# GPS_Board_Rev_C.net
KiCad netlist of a schematic drawn in EAGLE
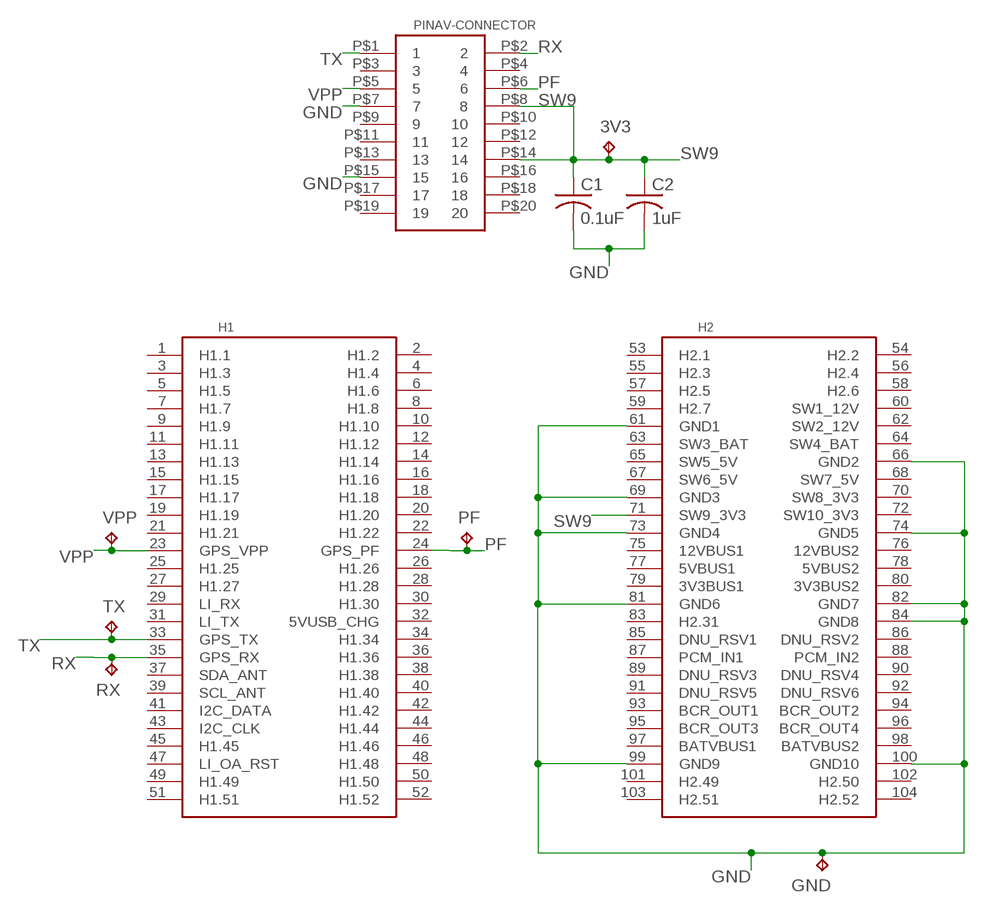
[diagram p0: schematic, sheet 1]

(export (version "E")
  (design (tool "Eeschema 10.0.6"))
  (components
    (comp (ref "3V3")
      (value "TPTP10SQ")
      (footprint "eagle-import:TP10SQ")
      (libsource (lib "eagle-import") (part "TPTP10SQ"))
    )
    (comp (ref "C1")
      (value "0.1uF")
      (footprint "eagle-import:C0805")
      (libsource (lib "eagle-import") (part "C-USC0805"))
    )
    (comp (ref "C2")
      (value "1uF")
      (footprint "eagle-import:C0805")
      (libsource (lib "eagle-import") (part "C-USC0805"))
    )
    (comp (ref "GND")
      (value "TPTP10SQ")
      (footprint "eagle-import:TP10SQ")
      (libsource (lib "eagle-import") (part "TPTP10SQ"))
    )
    (comp (ref "PF")
      (value "TPTP10SQ")
      (footprint "eagle-import:TP10SQ")
      (libsource (lib "eagle-import") (part "TPTP10SQ"))
    )
    (comp (ref "PINAV-CONNECTOR")
      (value "HLE-110-02-X-DVHLE-110-X-DV-PE-BA")
      (footprint "eagle-import:HLE-110-02-X-DV-PE-BE")
      (libsource (lib "eagle-import") (part "HLE-110-02-X-DVHLE-110-X-DV-PE-BA"))
    )
    (comp (ref "RX")
      (value "TPTP10SQ")
      (footprint "eagle-import:TP10SQ")
      (libsource (lib "eagle-import") (part "TPTP10SQ"))
    )
    (comp (ref "TX")
      (value "TPTP10SQ")
      (footprint "eagle-import:TP10SQ")
      (libsource (lib "eagle-import") (part "TPTP10SQ"))
    )
    (comp (ref "U$2")
      (value "PC104_NO_DIMENSION")
      (footprint "eagle-import:PC104_NO_DIMENSION")
      (libsource (lib "eagle-import") (part "PC104_NO_DIMENSION"))
    )
    (comp (ref "VPP")
      (value "TPTP10SQ")
      (footprint "eagle-import:TP10SQ")
      (libsource (lib "eagle-import") (part "TPTP10SQ"))
    )
  )
  (nets
    (net (code "1") (name "/GND") (class "Default")
      (node (ref "C1") (pin "2") (pinfunction "2_2") (pintype "passive"))
      (node (ref "C2") (pin "2") (pinfunction "2_2") (pintype "passive"))
      (node (ref "GND") (pin "TP") (pinfunction "TP_TP") (pintype "input"))
      (node (ref "PINAV-CONNECTOR") (pin "P$15") (pinfunction "15_P$15") (pintype "bidirectional"))
      (node (ref "PINAV-CONNECTOR") (pin "P$7") (pinfunction "7_P$7") (pintype "bidirectional"))
      (node (ref "U$2") (pin "100") (pinfunction "GND10_100") (pintype "bidirectional"))
      (node (ref "U$2") (pin "61") (pinfunction "GND1_61") (pintype "bidirectional"))
      (node (ref "U$2") (pin "66") (pinfunction "GND2_66") (pintype "bidirectional"))
      (node (ref "U$2") (pin "69") (pinfunction "GND3_69") (pintype "bidirectional"))
      (node (ref "U$2") (pin "73") (pinfunction "GND4_73") (pintype "bidirectional"))
      (node (ref "U$2") (pin "74") (pinfunction "GND5_74") (pintype "bidirectional"))
      (node (ref "U$2") (pin "81") (pinfunction "GND6_81") (pintype "bidirectional"))
      (node (ref "U$2") (pin "82") (pinfunction "GND7_82") (pintype "bidirectional"))
      (node (ref "U$2") (pin "84") (pinfunction "GND8_84") (pintype "bidirectional"))
      (node (ref "U$2") (pin "99") (pinfunction "GND9_99") (pintype "bidirectional"))
    )
    (net (code "2") (name "/PF") (class "Default")
      (node (ref "PF") (pin "TP") (pinfunction "TP_TP") (pintype "input"))
      (node (ref "PINAV-CONNECTOR") (pin "P$6") (pinfunction "6_P$6") (pintype "bidirectional"))
      (node (ref "U$2") (pin "24") (pinfunction "GPS_PF_24") (pintype "bidirectional"))
    )
    (net (code "3") (name "/RX") (class "Default")
      (node (ref "PINAV-CONNECTOR") (pin "P$2") (pinfunction "2_P$2") (pintype "bidirectional"))
      (node (ref "RX") (pin "TP") (pinfunction "TP_TP") (pintype "input"))
      (node (ref "U$2") (pin "35") (pinfunction "GPS_RX_35") (pintype "bidirectional"))
    )
    (net (code "4") (name "/SW9") (class "Default")
      (node (ref "3V3") (pin "TP") (pinfunction "TP_TP") (pintype "input"))
      (node (ref "C1") (pin "1") (pinfunction "1_1") (pintype "passive"))
      (node (ref "C2") (pin "1") (pinfunction "1_1") (pintype "passive"))
      (node (ref "PINAV-CONNECTOR") (pin "P$14") (pinfunction "14_P$14") (pintype "bidirectional"))
      (node (ref "PINAV-CONNECTOR") (pin "P$8") (pinfunction "8_P$8") (pintype "bidirectional"))
      (node (ref "U$2") (pin "71") (pinfunction "SW9_3V3_71") (pintype "bidirectional"))
    )
    (net (code "5") (name "/TX") (class "Default")
      (node (ref "PINAV-CONNECTOR") (pin "P$1") (pinfunction "1_P$1") (pintype "bidirectional"))
      (node (ref "TX") (pin "TP") (pinfunction "TP_TP") (pintype "input"))
      (node (ref "U$2") (pin "33") (pinfunction "GPS_TX_33") (pintype "bidirectional"))
    )
    (net (code "6") (name "/VPP") (class "Default")
      (node (ref "PINAV-CONNECTOR") (pin "P$5") (pinfunction "5_P$5") (pintype "bidirectional"))
      (node (ref "U$2") (pin "23") (pinfunction "GPS_VPP_23") (pintype "bidirectional"))
      (node (ref "VPP") (pin "TP") (pinfunction "TP_TP") (pintype "input"))
    )
    (net (code "7") (name "unconnected-(PINAV-CONNECTOR-3-PadP$3)") (class "Default")
      (node (ref "PINAV-CONNECTOR") (pin "P$3") (pinfunction "3_P$3") (pintype "bidirectional"))
    )
    (net (code "8") (name "unconnected-(PINAV-CONNECTOR-4-PadP$4)") (class "Default")
      (node (ref "PINAV-CONNECTOR") (pin "P$4") (pinfunction "4_P$4") (pintype "bidirectional"))
    )
    (net (code "9") (name "unconnected-(PINAV-CONNECTOR-9-PadP$9)") (class "Default")
      (node (ref "PINAV-CONNECTOR") (pin "P$9") (pinfunction "9_P$9") (pintype "bidirectional"))
    )
    (net (code "10") (name "unconnected-(PINAV-CONNECTOR-10-PadP$10)") (class "Default")
      (node (ref "PINAV-CONNECTOR") (pin "P$10") (pinfunction "10_P$10") (pintype "bidirectional"))
    )
    (net (code "11") (name "unconnected-(PINAV-CONNECTOR-11-PadP$11)") (class "Default")
      (node (ref "PINAV-CONNECTOR") (pin "P$11") (pinfunction "11_P$11") (pintype "bidirectional"))
    )
    (net (code "12") (name "unconnected-(PINAV-CONNECTOR-12-PadP$12)") (class "Default")
      (node (ref "PINAV-CONNECTOR") (pin "P$12") (pinfunction "12_P$12") (pintype "bidirectional"))
    )
    (net (code "13") (name "unconnected-(PINAV-CONNECTOR-13-PadP$13)") (class "Default")
      (node (ref "PINAV-CONNECTOR") (pin "P$13") (pinfunction "13_P$13") (pintype "bidirectional"))
    )
    (net (code "14") (name "unconnected-(PINAV-CONNECTOR-16-PadP$16)") (class "Default")
      (node (ref "PINAV-CONNECTOR") (pin "P$16") (pinfunction "16_P$16") (pintype "bidirectional"))
    )
    (net (code "15") (name "unconnected-(PINAV-CONNECTOR-17-PadP$17)") (class "Default")
      (node (ref "PINAV-CONNECTOR") (pin "P$17") (pinfunction "17_P$17") (pintype "bidirectional"))
    )
    (net (code "16") (name "unconnected-(PINAV-CONNECTOR-18-PadP$18)") (class "Default")
      (node (ref "PINAV-CONNECTOR") (pin "P$18") (pinfunction "18_P$18") (pintype "bidirectional"))
    )
    (net (code "17") (name "unconnected-(PINAV-CONNECTOR-19-PadP$19)") (class "Default")
      (node (ref "PINAV-CONNECTOR") (pin "P$19") (pinfunction "19_P$19") (pintype "bidirectional"))
    )
    (net (code "18") (name "unconnected-(PINAV-CONNECTOR-20-PadP$20)") (class "Default")
      (node (ref "PINAV-CONNECTOR") (pin "P$20") (pinfunction "20_P$20") (pintype "bidirectional"))
    )
    (net (code "19") (name "unconnected-(U$2-3V3BUS1-Pad79)") (class "Default")
      (node (ref "U$2") (pin "79") (pinfunction "3V3BUS1_79") (pintype "bidirectional"))
    )
    (net (code "20") (name "unconnected-(U$2-3V3BUS2-Pad80)") (class "Default")
      (node (ref "U$2") (pin "80") (pinfunction "3V3BUS2_80") (pintype "bidirectional"))
    )
    (net (code "21") (name "unconnected-(U$2-5VBUS1-Pad77)") (class "Default")
      (node (ref "U$2") (pin "77") (pinfunction "5VBUS1_77") (pintype "bidirectional"))
    )
    (net (code "22") (name "unconnected-(U$2-5VBUS2-Pad78)") (class "Default")
      (node (ref "U$2") (pin "78") (pinfunction "5VBUS2_78") (pintype "bidirectional"))
    )
    (net (code "23") (name "unconnected-(U$2-5VUSB_CHG-Pad32)") (class "Default")
      (node (ref "U$2") (pin "32") (pinfunction "5VUSB_CHG_32") (pintype "bidirectional"))
    )
    (net (code "24") (name "unconnected-(U$2-12VBUS1-Pad75)") (class "Default")
      (node (ref "U$2") (pin "75") (pinfunction "12VBUS1_75") (pintype "bidirectional"))
    )
    (net (code "25") (name "unconnected-(U$2-12VBUS2-Pad76)") (class "Default")
      (node (ref "U$2") (pin "76") (pinfunction "12VBUS2_76") (pintype "bidirectional"))
    )
    (net (code "26") (name "unconnected-(U$2-BATVBUS1-Pad97)") (class "Default")
      (node (ref "U$2") (pin "97") (pinfunction "BATVBUS1_97") (pintype "bidirectional"))
    )
    (net (code "27") (name "unconnected-(U$2-BATVBUS2-Pad98)") (class "Default")
      (node (ref "U$2") (pin "98") (pinfunction "BATVBUS2_98") (pintype "bidirectional"))
    )
    (net (code "28") (name "unconnected-(U$2-BCR_OUT1-Pad93)") (class "Default")
      (node (ref "U$2") (pin "93") (pinfunction "BCR_OUT1_93") (pintype "bidirectional"))
    )
    (net (code "29") (name "unconnected-(U$2-BCR_OUT2-Pad94)") (class "Default")
      (node (ref "U$2") (pin "94") (pinfunction "BCR_OUT2_94") (pintype "bidirectional"))
    )
    (net (code "30") (name "unconnected-(U$2-BCR_OUT3-Pad95)") (class "Default")
      (node (ref "U$2") (pin "95") (pinfunction "BCR_OUT3_95") (pintype "bidirectional"))
    )
    (net (code "31") (name "unconnected-(U$2-BCR_OUT4-Pad96)") (class "Default")
      (node (ref "U$2") (pin "96") (pinfunction "BCR_OUT4_96") (pintype "bidirectional"))
    )
    (net (code "32") (name "unconnected-(U$2-DNU_RSV1-Pad85)") (class "Default")
      (node (ref "U$2") (pin "85") (pinfunction "DNU_RSV1_85") (pintype "bidirectional"))
    )
    (net (code "33") (name "unconnected-(U$2-DNU_RSV2-Pad86)") (class "Default")
      (node (ref "U$2") (pin "86") (pinfunction "DNU_RSV2_86") (pintype "bidirectional"))
    )
    (net (code "34") (name "unconnected-(U$2-DNU_RSV3-Pad89)") (class "Default")
      (node (ref "U$2") (pin "89") (pinfunction "DNU_RSV3_89") (pintype "bidirectional"))
    )
    (net (code "35") (name "unconnected-(U$2-DNU_RSV4-Pad90)") (class "Default")
      (node (ref "U$2") (pin "90") (pinfunction "DNU_RSV4_90") (pintype "bidirectional"))
    )
    (net (code "36") (name "unconnected-(U$2-DNU_RSV5-Pad91)") (class "Default")
      (node (ref "U$2") (pin "91") (pinfunction "DNU_RSV5_91") (pintype "bidirectional"))
    )
    (net (code "37") (name "unconnected-(U$2-DNU_RSV6-Pad92)") (class "Default")
      (node (ref "U$2") (pin "92") (pinfunction "DNU_RSV6_92") (pintype "bidirectional"))
    )
    (net (code "38") (name "unconnected-(U$2-H1.1-Pad1)") (class "Default")
      (node (ref "U$2") (pin "1") (pinfunction "H1.1_1") (pintype "bidirectional"))
    )
    (net (code "39") (name "unconnected-(U$2-H1.2-Pad2)") (class "Default")
      (node (ref "U$2") (pin "2") (pinfunction "H1.2_2") (pintype "bidirectional"))
    )
    (net (code "40") (name "unconnected-(U$2-H1.3-Pad3)") (class "Default")
      (node (ref "U$2") (pin "3") (pinfunction "H1.3_3") (pintype "bidirectional"))
    )
    (net (code "41") (name "unconnected-(U$2-H1.4-Pad4)") (class "Default")
      (node (ref "U$2") (pin "4") (pinfunction "H1.4_4") (pintype "bidirectional"))
    )
    (net (code "42") (name "unconnected-(U$2-H1.5-Pad5)") (class "Default")
      (node (ref "U$2") (pin "5") (pinfunction "H1.5_5") (pintype "bidirectional"))
    )
    (net (code "43") (name "unconnected-(U$2-H1.6-Pad6)") (class "Default")
      (node (ref "U$2") (pin "6") (pinfunction "H1.6_6") (pintype "bidirectional"))
    )
    (net (code "44") (name "unconnected-(U$2-H1.7-Pad7)") (class "Default")
      (node (ref "U$2") (pin "7") (pinfunction "H1.7_7") (pintype "bidirectional"))
    )
    (net (code "45") (name "unconnected-(U$2-H1.8-Pad8)") (class "Default")
      (node (ref "U$2") (pin "8") (pinfunction "H1.8_8") (pintype "bidirectional"))
    )
    (net (code "46") (name "unconnected-(U$2-H1.9-Pad9)") (class "Default")
      (node (ref "U$2") (pin "9") (pinfunction "H1.9_9") (pintype "bidirectional"))
    )
    (net (code "47") (name "unconnected-(U$2-H1.10-Pad10)") (class "Default")
      (node (ref "U$2") (pin "10") (pinfunction "H1.10_10") (pintype "bidirectional"))
    )
    (net (code "48") (name "unconnected-(U$2-H1.11-Pad11)") (class "Default")
      (node (ref "U$2") (pin "11") (pinfunction "H1.11_11") (pintype "bidirectional"))
    )
    (net (code "49") (name "unconnected-(U$2-H1.12-Pad12)") (class "Default")
      (node (ref "U$2") (pin "12") (pinfunction "H1.12_12") (pintype "bidirectional"))
    )
    (net (code "50") (name "unconnected-(U$2-H1.13-Pad13)") (class "Default")
      (node (ref "U$2") (pin "13") (pinfunction "H1.13_13") (pintype "bidirectional"))
    )
    (net (code "51") (name "unconnected-(U$2-H1.14-Pad14)") (class "Default")
      (node (ref "U$2") (pin "14") (pinfunction "H1.14_14") (pintype "bidirectional"))
    )
    (net (code "52") (name "unconnected-(U$2-H1.15-Pad15)") (class "Default")
      (node (ref "U$2") (pin "15") (pinfunction "H1.15_15") (pintype "bidirectional"))
    )
    (net (code "53") (name "unconnected-(U$2-H1.16-Pad16)") (class "Default")
      (node (ref "U$2") (pin "16") (pinfunction "H1.16_16") (pintype "bidirectional"))
    )
    (net (code "54") (name "unconnected-(U$2-H1.17-Pad17)") (class "Default")
      (node (ref "U$2") (pin "17") (pinfunction "H1.17_17") (pintype "bidirectional"))
    )
    (net (code "55") (name "unconnected-(U$2-H1.18-Pad18)") (class "Default")
      (node (ref "U$2") (pin "18") (pinfunction "H1.18_18") (pintype "bidirectional"))
    )
    (net (code "56") (name "unconnected-(U$2-H1.19-Pad19)") (class "Default")
      (node (ref "U$2") (pin "19") (pinfunction "H1.19_19") (pintype "bidirectional"))
    )
    (net (code "57") (name "unconnected-(U$2-H1.20-Pad20)") (class "Default")
      (node (ref "U$2") (pin "20") (pinfunction "H1.20_20") (pintype "bidirectional"))
    )
    (net (code "58") (name "unconnected-(U$2-H1.21-Pad21)") (class "Default")
      (node (ref "U$2") (pin "21") (pinfunction "H1.21_21") (pintype "bidirectional"))
    )
    (net (code "59") (name "unconnected-(U$2-H1.22-Pad22)") (class "Default")
      (node (ref "U$2") (pin "22") (pinfunction "H1.22_22") (pintype "bidirectional"))
    )
    (net (code "60") (name "unconnected-(U$2-H1.25-Pad25)") (class "Default")
      (node (ref "U$2") (pin "25") (pinfunction "H1.25_25") (pintype "bidirectional"))
    )
    (net (code "61") (name "unconnected-(U$2-H1.26-Pad26)") (class "Default")
      (node (ref "U$2") (pin "26") (pinfunction "H1.26_26") (pintype "bidirectional"))
    )
    (net (code "62") (name "unconnected-(U$2-H1.27-Pad27)") (class "Default")
      (node (ref "U$2") (pin "27") (pinfunction "H1.27_27") (pintype "bidirectional"))
    )
    (net (code "63") (name "unconnected-(U$2-H1.28-Pad28)") (class "Default")
      (node (ref "U$2") (pin "28") (pinfunction "H1.28_28") (pintype "bidirectional"))
    )
    (net (code "64") (name "unconnected-(U$2-H1.30-Pad30)") (class "Default")
      (node (ref "U$2") (pin "30") (pinfunction "H1.30_30") (pintype "bidirectional"))
    )
    (net (code "65") (name "unconnected-(U$2-H1.34-Pad34)") (class "Default")
      (node (ref "U$2") (pin "34") (pinfunction "H1.34_34") (pintype "bidirectional"))
    )
    (net (code "66") (name "unconnected-(U$2-H1.36-Pad36)") (class "Default")
      (node (ref "U$2") (pin "36") (pinfunction "H1.36_36") (pintype "bidirectional"))
    )
    (net (code "67") (name "unconnected-(U$2-H1.38-Pad38)") (class "Default")
      (node (ref "U$2") (pin "38") (pinfunction "H1.38_38") (pintype "bidirectional"))
    )
    (net (code "68") (name "unconnected-(U$2-H1.40-Pad40)") (class "Default")
      (node (ref "U$2") (pin "40") (pinfunction "H1.40_40") (pintype "bidirectional"))
    )
    (net (code "69") (name "unconnected-(U$2-H1.42-Pad42)") (class "Default")
      (node (ref "U$2") (pin "42") (pinfunction "H1.42_42") (pintype "bidirectional"))
    )
    (net (code "70") (name "unconnected-(U$2-H1.44-Pad44)") (class "Default")
      (node (ref "U$2") (pin "44") (pinfunction "H1.44_44") (pintype "bidirectional"))
    )
    (net (code "71") (name "unconnected-(U$2-H1.45-Pad45)") (class "Default")
      (node (ref "U$2") (pin "45") (pinfunction "H1.45_45") (pintype "bidirectional"))
    )
    (net (code "72") (name "unconnected-(U$2-H1.46-Pad46)") (class "Default")
      (node (ref "U$2") (pin "46") (pinfunction "H1.46_46") (pintype "bidirectional"))
    )
    (net (code "73") (name "unconnected-(U$2-H1.48-Pad48)") (class "Default")
      (node (ref "U$2") (pin "48") (pinfunction "H1.48_48") (pintype "bidirectional"))
    )
    (net (code "74") (name "unconnected-(U$2-H1.49-Pad49)") (class "Default")
      (node (ref "U$2") (pin "49") (pinfunction "H1.49_49") (pintype "bidirectional"))
    )
    (net (code "75") (name "unconnected-(U$2-H1.50-Pad50)") (class "Default")
      (node (ref "U$2") (pin "50") (pinfunction "H1.50_50") (pintype "bidirectional"))
    )
    (net (code "76") (name "unconnected-(U$2-H1.51-Pad51)") (class "Default")
      (node (ref "U$2") (pin "51") (pinfunction "H1.51_51") (pintype "bidirectional"))
    )
    (net (code "77") (name "unconnected-(U$2-H1.52-Pad52)") (class "Default")
      (node (ref "U$2") (pin "52") (pinfunction "H1.52_52") (pintype "bidirectional"))
    )
    (net (code "78") (name "unconnected-(U$2-H2.1-Pad53)") (class "Default")
      (node (ref "U$2") (pin "53") (pinfunction "H2.1_53") (pintype "bidirectional"))
    )
    (net (code "79") (name "unconnected-(U$2-H2.2-Pad54)") (class "Default")
      (node (ref "U$2") (pin "54") (pinfunction "H2.2_54") (pintype "bidirectional"))
    )
    (net (code "80") (name "unconnected-(U$2-H2.3-Pad55)") (class "Default")
      (node (ref "U$2") (pin "55") (pinfunction "H2.3_55") (pintype "bidirectional"))
    )
    (net (code "81") (name "unconnected-(U$2-H2.4-Pad56)") (class "Default")
      (node (ref "U$2") (pin "56") (pinfunction "H2.4_56") (pintype "bidirectional"))
    )
    (net (code "82") (name "unconnected-(U$2-H2.5-Pad57)") (class "Default")
      (node (ref "U$2") (pin "57") (pinfunction "H2.5_57") (pintype "bidirectional"))
    )
    (net (code "83") (name "unconnected-(U$2-H2.6-Pad58)") (class "Default")
      (node (ref "U$2") (pin "58") (pinfunction "H2.6_58") (pintype "bidirectional"))
    )
    (net (code "84") (name "unconnected-(U$2-H2.7-Pad59)") (class "Default")
      (node (ref "U$2") (pin "59") (pinfunction "H2.7_59") (pintype "bidirectional"))
    )
    (net (code "85") (name "unconnected-(U$2-H2.31-Pad83)") (class "Default")
      (node (ref "U$2") (pin "83") (pinfunction "H2.31_83") (pintype "bidirectional"))
    )
    (net (code "86") (name "unconnected-(U$2-H2.49-Pad101)") (class "Default")
      (node (ref "U$2") (pin "101") (pinfunction "H2.49_101") (pintype "bidirectional"))
    )
    (net (code "87") (name "unconnected-(U$2-H2.50-Pad102)") (class "Default")
      (node (ref "U$2") (pin "102") (pinfunction "H2.50_102") (pintype "bidirectional"))
    )
    (net (code "88") (name "unconnected-(U$2-H2.51-Pad103)") (class "Default")
      (node (ref "U$2") (pin "103") (pinfunction "H2.51_103") (pintype "bidirectional"))
    )
    (net (code "89") (name "unconnected-(U$2-H2.52-Pad104)") (class "Default")
      (node (ref "U$2") (pin "104") (pinfunction "H2.52_104") (pintype "bidirectional"))
    )
    (net (code "90") (name "unconnected-(U$2-I2C_CLK-Pad43)") (class "Default")
      (node (ref "U$2") (pin "43") (pinfunction "I2C_CLK_43") (pintype "bidirectional"))
    )
    (net (code "91") (name "unconnected-(U$2-I2C_DATA-Pad41)") (class "Default")
      (node (ref "U$2") (pin "41") (pinfunction "I2C_DATA_41") (pintype "bidirectional"))
    )
    (net (code "92") (name "unconnected-(U$2-LI_OA_RST-Pad47)") (class "Default")
      (node (ref "U$2") (pin "47") (pinfunction "LI_OA_RST_47") (pintype "bidirectional"))
    )
    (net (code "93") (name "unconnected-(U$2-LI_RX-Pad29)") (class "Default")
      (node (ref "U$2") (pin "29") (pinfunction "LI_RX_29") (pintype "bidirectional"))
    )
    (net (code "94") (name "unconnected-(U$2-LI_TX-Pad31)") (class "Default")
      (node (ref "U$2") (pin "31") (pinfunction "LI_TX_31") (pintype "bidirectional"))
    )
    (net (code "95") (name "unconnected-(U$2-PCM_IN1-Pad87)") (class "Default")
      (node (ref "U$2") (pin "87") (pinfunction "PCM_IN1_87") (pintype "bidirectional"))
    )
    (net (code "96") (name "unconnected-(U$2-PCM_IN2-Pad88)") (class "Default")
      (node (ref "U$2") (pin "88") (pinfunction "PCM_IN2_88") (pintype "bidirectional"))
    )
    (net (code "97") (name "unconnected-(U$2-SCL_ANT-Pad39)") (class "Default")
      (node (ref "U$2") (pin "39") (pinfunction "SCL_ANT_39") (pintype "bidirectional"))
    )
    (net (code "98") (name "unconnected-(U$2-SDA_ANT-Pad37)") (class "Default")
      (node (ref "U$2") (pin "37") (pinfunction "SDA_ANT_37") (pintype "bidirectional"))
    )
    (net (code "99") (name "unconnected-(U$2-SW1_12V-Pad60)") (class "Default")
      (node (ref "U$2") (pin "60") (pinfunction "SW1_12V_60") (pintype "bidirectional"))
    )
    (net (code "100") (name "unconnected-(U$2-SW2_12V-Pad62)") (class "Default")
      (node (ref "U$2") (pin "62") (pinfunction "SW2_12V_62") (pintype "bidirectional"))
    )
    (net (code "101") (name "unconnected-(U$2-SW3_BAT-Pad63)") (class "Default")
      (node (ref "U$2") (pin "63") (pinfunction "SW3_BAT_63") (pintype "bidirectional"))
    )
    (net (code "102") (name "unconnected-(U$2-SW4_BAT-Pad64)") (class "Default")
      (node (ref "U$2") (pin "64") (pinfunction "SW4_BAT_64") (pintype "bidirectional"))
    )
    (net (code "103") (name "unconnected-(U$2-SW5_5V-Pad65)") (class "Default")
      (node (ref "U$2") (pin "65") (pinfunction "SW5_5V_65") (pintype "bidirectional"))
    )
    (net (code "104") (name "unconnected-(U$2-SW6_5V-Pad67)") (class "Default")
      (node (ref "U$2") (pin "67") (pinfunction "SW6_5V_67") (pintype "bidirectional"))
    )
    (net (code "105") (name "unconnected-(U$2-SW7_5V-Pad68)") (class "Default")
      (node (ref "U$2") (pin "68") (pinfunction "SW7_5V_68") (pintype "bidirectional"))
    )
    (net (code "106") (name "unconnected-(U$2-SW8_3V3-Pad70)") (class "Default")
      (node (ref "U$2") (pin "70") (pinfunction "SW8_3V3_70") (pintype "bidirectional"))
    )
    (net (code "107") (name "unconnected-(U$2-SW10_3V3-Pad72)") (class "Default")
      (node (ref "U$2") (pin "72") (pinfunction "SW10_3V3_72") (pintype "bidirectional"))
    )
  )
)
